# quad-wireless-switch.net
KiCad netlist of a schematic drawn in EAGLE
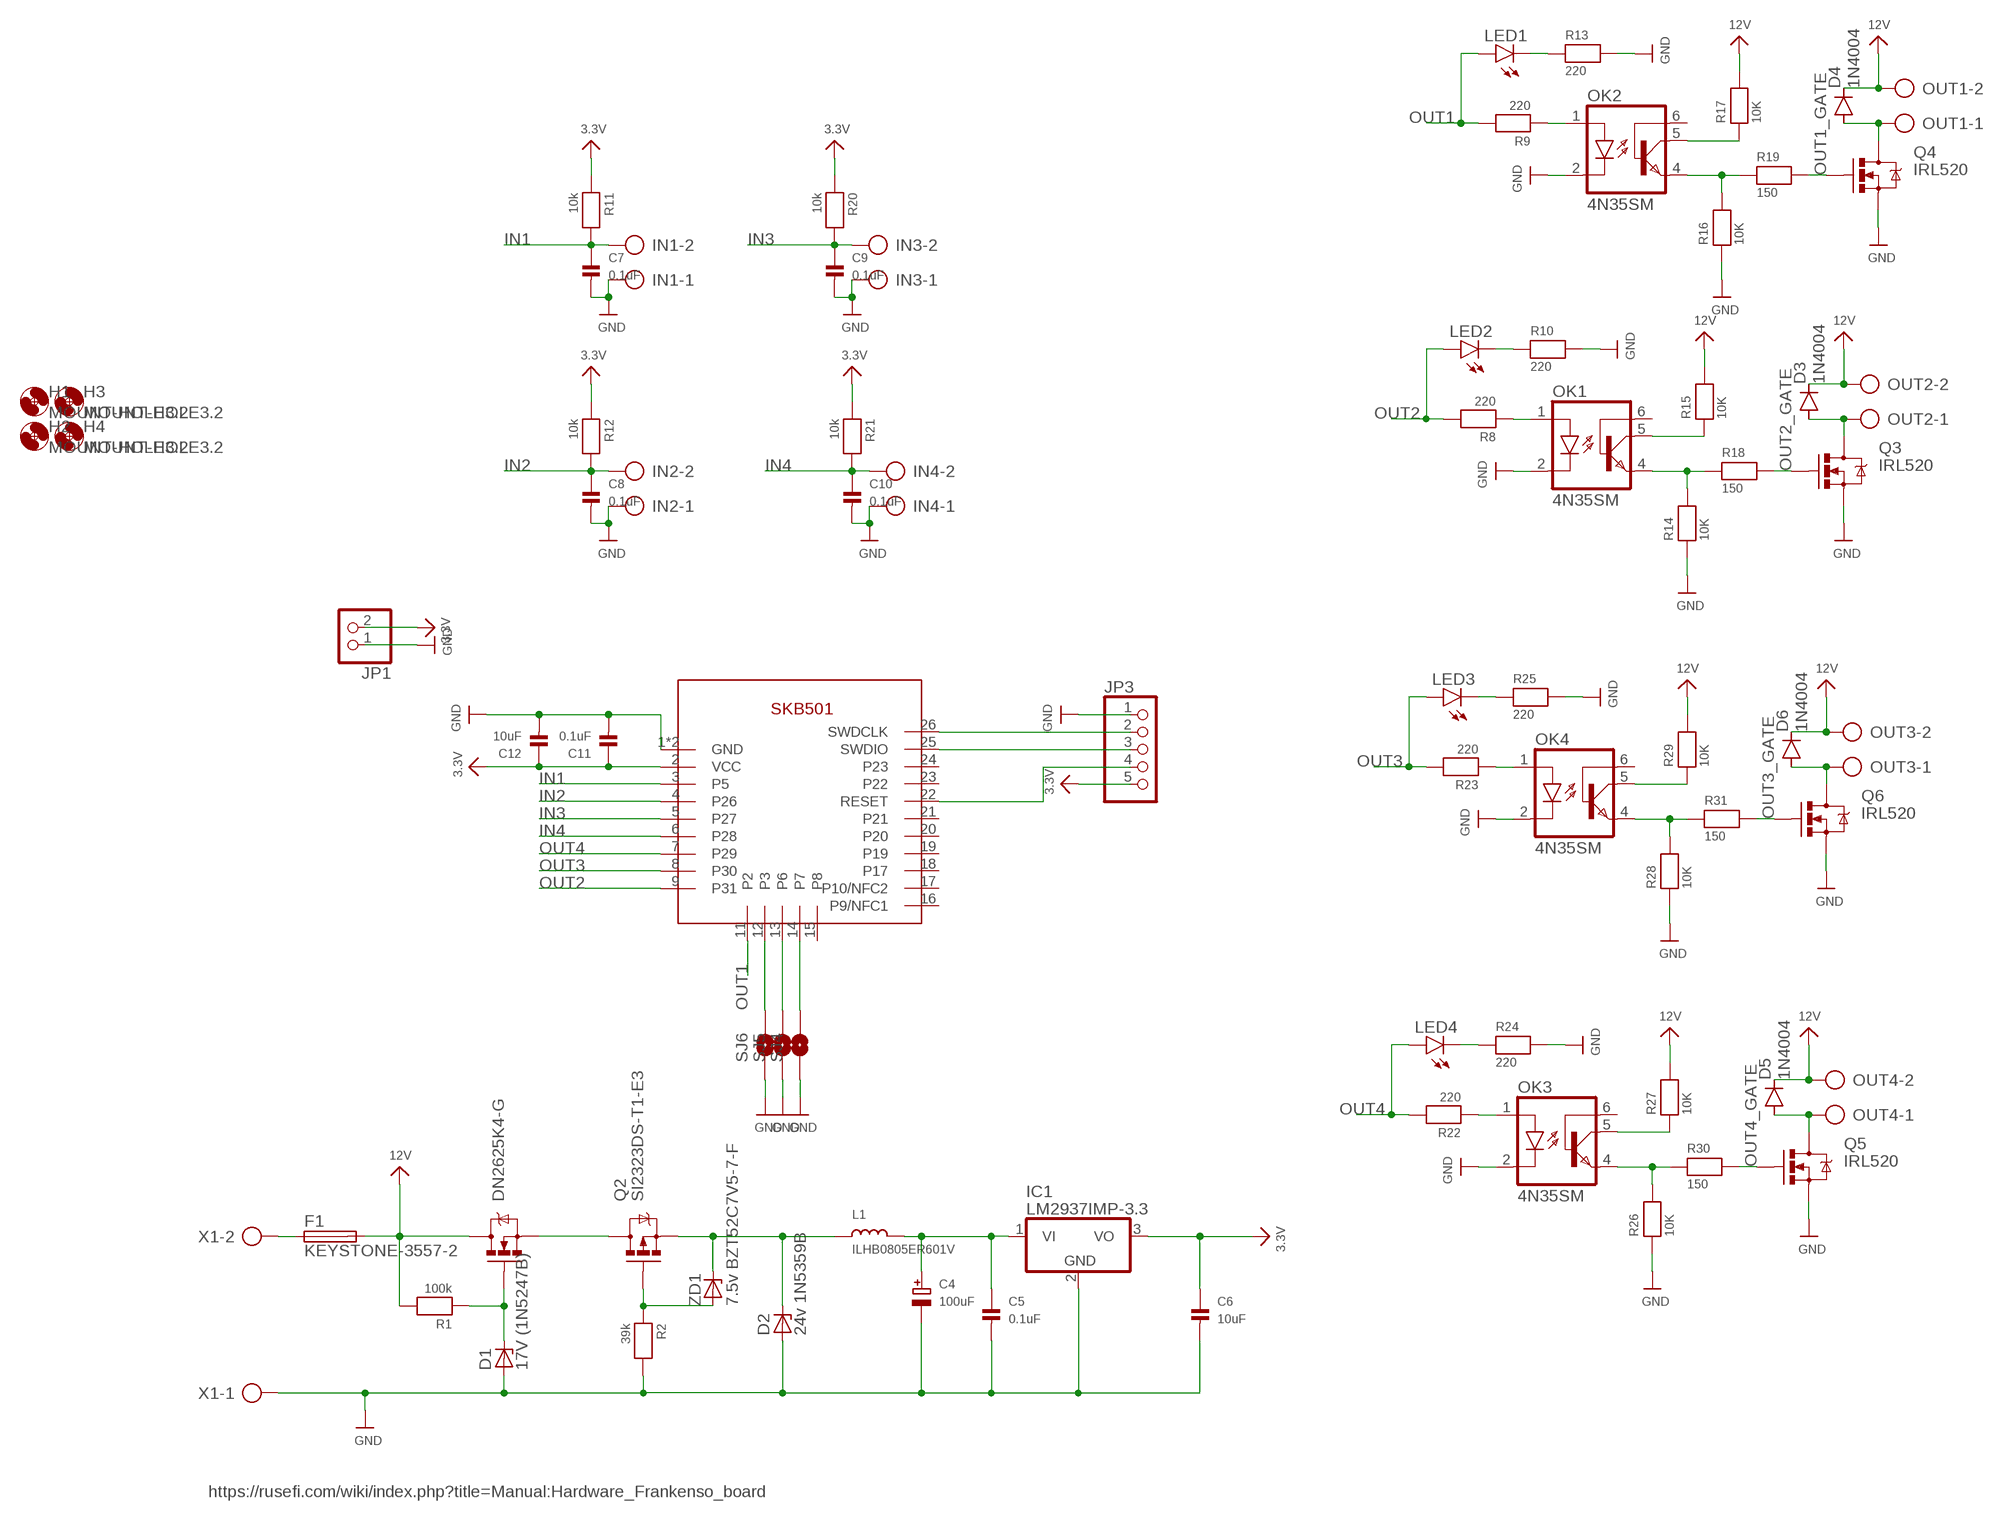
[diagram p0: schematic, sheet 1]

(export (version "E")
  (design (tool "Eeschema 10.0.6"))
  (components
    (comp (ref "C4")
      (value "100uF")
      (footprint "eagle-import:PANASONIC_D")
      (libsource (lib "eagle-import") (part "CAP_ELECTROLYTICPANASONIC_D"))
    )
    (comp (ref "C5")
      (value "0.1uF")
      (footprint "eagle-import:0805")
      (libsource (lib "eagle-import") (part "CAP_CERAMIC0805"))
    )
    (comp (ref "C6")
      (value "10uF")
      (footprint "eagle-import:0805")
      (libsource (lib "eagle-import") (part "CAP_CERAMIC0805"))
    )
    (comp (ref "C7")
      (value "0.1uF")
      (footprint "eagle-import:0805")
      (libsource (lib "eagle-import") (part "CAP_CERAMIC0805"))
    )
    (comp (ref "C8")
      (value "0.1uF")
      (footprint "eagle-import:0805")
      (libsource (lib "eagle-import") (part "CAP_CERAMIC0805"))
    )
    (comp (ref "C9")
      (value "0.1uF")
      (footprint "eagle-import:0805")
      (libsource (lib "eagle-import") (part "CAP_CERAMIC0805"))
    )
    (comp (ref "C10")
      (value "0.1uF")
      (footprint "eagle-import:0805")
      (libsource (lib "eagle-import") (part "CAP_CERAMIC0805"))
    )
    (comp (ref "C11")
      (value "0.1uF")
      (footprint "eagle-import:0805")
      (libsource (lib "eagle-import") (part "CAP_CERAMIC0805"))
    )
    (comp (ref "C12")
      (value "10uF")
      (footprint "eagle-import:0805")
      (libsource (lib "eagle-import") (part "CAP_CERAMIC0805"))
    )
    (comp (ref "D1")
      (value "17V (1N5247B)")
      (footprint "eagle-import:ZDIO-5")
      (libsource (lib "eagle-import") (part "ZENER-DIODEZD-5"))
    )
    (comp (ref "D2")
      (value "24v 1N5359B")
      (footprint "eagle-import:DO41Z10")
      (libsource (lib "eagle-import") (part "ZPY"))
    )
    (comp (ref "D3")
      (value "1N4004")
      (footprint "eagle-import:DO41-10")
      (libsource (lib "eagle-import") (part "1N4004"))
    )
    (comp (ref "D4")
      (value "1N4004")
      (footprint "eagle-import:DO41-10")
      (libsource (lib "eagle-import") (part "1N4004"))
    )
    (comp (ref "D5")
      (value "1N4004")
      (footprint "eagle-import:DO41-10")
      (libsource (lib "eagle-import") (part "1N4004"))
    )
    (comp (ref "D6")
      (value "1N4004")
      (footprint "eagle-import:DO41-10")
      (libsource (lib "eagle-import") (part "1N4004"))
    )
    (comp (ref "F1")
      (value "KEYSTONE-3557-2")
      (footprint "eagle-import:KEYSTONE-3557-2")
      (libsource (lib "eagle-import") (part "KEYSTONE-3557-2"))
    )
    (comp (ref "H1")
      (value "MOUNT-HOLE3.2")
      (footprint "eagle-import:3,2")
      (libsource (lib "eagle-import") (part "MOUNT-HOLE3.2"))
    )
    (comp (ref "H2")
      (value "MOUNT-HOLE3.2")
      (footprint "eagle-import:3,2")
      (libsource (lib "eagle-import") (part "MOUNT-HOLE3.2"))
    )
    (comp (ref "H3")
      (value "MOUNT-HOLE3.2")
      (footprint "eagle-import:3,2")
      (libsource (lib "eagle-import") (part "MOUNT-HOLE3.2"))
    )
    (comp (ref "H4")
      (value "MOUNT-HOLE3.2")
      (footprint "eagle-import:3,2")
      (libsource (lib "eagle-import") (part "MOUNT-HOLE3.2"))
    )
    (comp (ref "IC1")
      (value "LM2937IMP-3.3")
      (footprint "eagle-import:TO263-3")
      (libsource (lib "eagle-import") (part "LM2937"))
    )
    (comp (ref "IN1")
      (value "AK500/2-H")
      (footprint "eagle-import:AK500_2-H")
      (libsource (lib "eagle-import") (part "AK500/2-H"))
    )
    (comp (ref "IN2")
      (value "AK500/2-H")
      (footprint "eagle-import:AK500_2-H")
      (libsource (lib "eagle-import") (part "AK500/2-H"))
    )
    (comp (ref "IN3")
      (value "AK500/2-H")
      (footprint "eagle-import:AK500_2-H")
      (libsource (lib "eagle-import") (part "AK500/2-H"))
    )
    (comp (ref "IN4")
      (value "AK500/2-H")
      (footprint "eagle-import:AK500_2-H")
      (libsource (lib "eagle-import") (part "AK500/2-H"))
    )
    (comp (ref "JP1")
      (value "PINHD-1X2")
      (footprint "eagle-import:1X02")
      (libsource (lib "eagle-import") (part "PINHD-1X2"))
    )
    (comp (ref "JP3")
      (value "PINHD-1X5")
      (footprint "eagle-import:1X05")
      (libsource (lib "eagle-import") (part "PINHD-1X5"))
    )
    (comp (ref "L1")
      (value "ILHB0805ER601V")
      (footprint "eagle-import:0805")
      (libsource (lib "eagle-import") (part "INDUCTOR0805"))
    )
    (comp (ref "LED1")
      (value "LED5MM")
      (footprint "eagle-import:LED5MM")
      (libsource (lib "eagle-import") (part "LED5MM"))
    )
    (comp (ref "LED2")
      (value "LED5MM")
      (footprint "eagle-import:LED5MM")
      (libsource (lib "eagle-import") (part "LED5MM"))
    )
    (comp (ref "LED3")
      (value "LED5MM")
      (footprint "eagle-import:LED5MM")
      (libsource (lib "eagle-import") (part "LED5MM"))
    )
    (comp (ref "LED4")
      (value "LED5MM")
      (footprint "eagle-import:LED5MM")
      (libsource (lib "eagle-import") (part "LED5MM"))
    )
    (comp (ref "OK1")
      (value "4N35SM")
      (footprint "eagle-import:DIL6-SMD")
      (fields (field (name "MF") "FAIRCHILD SEMICONDUCTOR") (field (name "MPN") "4N35S-M"))
      (libsource (lib "eagle-import") (part "4N?MS35"))
    )
    (comp (ref "OK2")
      (value "4N35SM")
      (footprint "eagle-import:DIL6-SMD")
      (fields (field (name "MF") "FAIRCHILD SEMICONDUCTOR") (field (name "MPN") "4N35S-M"))
      (libsource (lib "eagle-import") (part "4N?MS35"))
    )
    (comp (ref "OK3")
      (value "4N35SM")
      (footprint "eagle-import:DIL6-SMD")
      (fields (field (name "MF") "FAIRCHILD SEMICONDUCTOR") (field (name "MPN") "4N35S-M"))
      (libsource (lib "eagle-import") (part "4N?MS35"))
    )
    (comp (ref "OK4")
      (value "4N35SM")
      (footprint "eagle-import:DIL6-SMD")
      (fields (field (name "MF") "FAIRCHILD SEMICONDUCTOR") (field (name "MPN") "4N35S-M"))
      (libsource (lib "eagle-import") (part "4N?MS35"))
    )
    (comp (ref "OUT1")
      (value "AK500/2-H")
      (footprint "eagle-import:AK500_2-H")
      (libsource (lib "eagle-import") (part "AK500/2-H"))
    )
    (comp (ref "OUT2")
      (value "AK500/2-H")
      (footprint "eagle-import:AK500_2-H")
      (libsource (lib "eagle-import") (part "AK500/2-H"))
    )
    (comp (ref "OUT3")
      (value "AK500/2-H")
      (footprint "eagle-import:AK500_2-H")
      (libsource (lib "eagle-import") (part "AK500/2-H"))
    )
    (comp (ref "OUT4")
      (value "AK500/2-H")
      (footprint "eagle-import:AK500_2-H")
      (libsource (lib "eagle-import") (part "AK500/2-H"))
    )
    (comp (ref "Q1")
      (value "DN2625K4-G")
      (footprint "eagle-import:DPAK")
      (libsource (lib "eagle-import") (part "MOSFET-NCHANNELFDD8780"))
    )
    (comp (ref "Q2")
      (value "SI2323DS-T1-E3")
      (footprint "eagle-import:SOT23-3")
      (libsource (lib "eagle-import") (part "MOSFET-PCHANNEL"))
    )
    (comp (ref "Q3")
      (value "IRL520")
      (footprint "eagle-import:TO220V")
      (libsource (lib "eagle-import") (part "keves-ng_1429743_MOSFET-NCHANNELFQP30N06L"))
    )
    (comp (ref "Q4")
      (value "IRL520")
      (footprint "eagle-import:TO220V")
      (libsource (lib "eagle-import") (part "keves-ng_1429743_MOSFET-NCHANNELFQP30N06L"))
    )
    (comp (ref "Q5")
      (value "IRL520")
      (footprint "eagle-import:TO220V")
      (libsource (lib "eagle-import") (part "keves-ng_1429743_MOSFET-NCHANNELFQP30N06L"))
    )
    (comp (ref "Q6")
      (value "IRL520")
      (footprint "eagle-import:TO220V")
      (libsource (lib "eagle-import") (part "keves-ng_1429743_MOSFET-NCHANNELFQP30N06L"))
    )
    (comp (ref "R1")
      (value "100k")
      (footprint "eagle-import:0805")
      (libsource (lib "eagle-import") (part "RESISTOR0805"))
    )
    (comp (ref "R2")
      (value "39k")
      (footprint "eagle-import:0805")
      (libsource (lib "eagle-import") (part "RESISTOR0805"))
    )
    (comp (ref "R8")
      (value "220")
      (footprint "eagle-import:0805")
      (libsource (lib "eagle-import") (part "RESISTOR0805"))
    )
    (comp (ref "R9")
      (value "220")
      (footprint "eagle-import:0805")
      (libsource (lib "eagle-import") (part "RESISTOR0805"))
    )
    (comp (ref "R10")
      (value "220")
      (footprint "eagle-import:0805")
      (libsource (lib "eagle-import") (part "RESISTOR0805"))
    )
    (comp (ref "R11")
      (value "10k")
      (footprint "eagle-import:0805")
      (libsource (lib "eagle-import") (part "RESISTOR0805"))
    )
    (comp (ref "R12")
      (value "10k")
      (footprint "eagle-import:0805")
      (libsource (lib "eagle-import") (part "RESISTOR0805"))
    )
    (comp (ref "R13")
      (value "220")
      (footprint "eagle-import:0805")
      (libsource (lib "eagle-import") (part "RESISTOR0805"))
    )
    (comp (ref "R14")
      (value "10K")
      (footprint "eagle-import:0805")
      (libsource (lib "eagle-import") (part "RESISTOR0805"))
    )
    (comp (ref "R15")
      (value "10K")
      (footprint "eagle-import:0805")
      (libsource (lib "eagle-import") (part "RESISTOR0805"))
    )
    (comp (ref "R16")
      (value "10K")
      (footprint "eagle-import:0805")
      (libsource (lib "eagle-import") (part "RESISTOR0805"))
    )
    (comp (ref "R17")
      (value "10K")
      (footprint "eagle-import:0805")
      (libsource (lib "eagle-import") (part "RESISTOR0805"))
    )
    (comp (ref "R18")
      (value "150")
      (footprint "eagle-import:0805")
      (libsource (lib "eagle-import") (part "RESISTOR0805"))
    )
    (comp (ref "R19")
      (value "150")
      (footprint "eagle-import:0805")
      (libsource (lib "eagle-import") (part "RESISTOR0805"))
    )
    (comp (ref "R20")
      (value "10k")
      (footprint "eagle-import:0805")
      (libsource (lib "eagle-import") (part "RESISTOR0805"))
    )
    (comp (ref "R21")
      (value "10k")
      (footprint "eagle-import:0805")
      (libsource (lib "eagle-import") (part "RESISTOR0805"))
    )
    (comp (ref "R22")
      (value "220")
      (footprint "eagle-import:0805")
      (libsource (lib "eagle-import") (part "RESISTOR0805"))
    )
    (comp (ref "R23")
      (value "220")
      (footprint "eagle-import:0805")
      (libsource (lib "eagle-import") (part "RESISTOR0805"))
    )
    (comp (ref "R24")
      (value "220")
      (footprint "eagle-import:0805")
      (libsource (lib "eagle-import") (part "RESISTOR0805"))
    )
    (comp (ref "R25")
      (value "220")
      (footprint "eagle-import:0805")
      (libsource (lib "eagle-import") (part "RESISTOR0805"))
    )
    (comp (ref "R26")
      (value "10K")
      (footprint "eagle-import:0805")
      (libsource (lib "eagle-import") (part "RESISTOR0805"))
    )
    (comp (ref "R27")
      (value "10K")
      (footprint "eagle-import:0805")
      (libsource (lib "eagle-import") (part "RESISTOR0805"))
    )
    (comp (ref "R28")
      (value "10K")
      (footprint "eagle-import:0805")
      (libsource (lib "eagle-import") (part "RESISTOR0805"))
    )
    (comp (ref "R29")
      (value "10K")
      (footprint "eagle-import:0805")
      (libsource (lib "eagle-import") (part "RESISTOR0805"))
    )
    (comp (ref "R30")
      (value "150")
      (footprint "eagle-import:0805")
      (libsource (lib "eagle-import") (part "RESISTOR0805"))
    )
    (comp (ref "R31")
      (value "150")
      (footprint "eagle-import:0805")
      (libsource (lib "eagle-import") (part "RESISTOR0805"))
    )
    (comp (ref "SJ4")
      (value "SOLDERJUMPERNO")
      (footprint "eagle-import:SJ_2S-NO")
      (libsource (lib "eagle-import") (part "SOLDERJUMPERNO"))
    )
    (comp (ref "SJ5")
      (value "SOLDERJUMPERNO")
      (footprint "eagle-import:SJ_2S-NO")
      (libsource (lib "eagle-import") (part "SOLDERJUMPERNO"))
    )
    (comp (ref "SJ6")
      (value "SOLDERJUMPERNO")
      (footprint "eagle-import:SJ_2S-NO")
      (libsource (lib "eagle-import") (part "SOLDERJUMPERNO"))
    )
    (comp (ref "U2")
      (value "SDB501")
      (footprint "eagle-import:SKB501")
      (libsource (lib "eagle-import") (part "SDB501"))
    )
    (comp (ref "X1")
      (value "AK500/2-H")
      (footprint "eagle-import:AK500_2-H")
      (libsource (lib "eagle-import") (part "AK500/2-H"))
    )
    (comp (ref "ZD1")
      (value "7.5v BZT52C7V5-7-F")
      (footprint "eagle-import:SOD123")
      (libsource (lib "eagle-import") (part "ZD-SOD123"))
    )
  )
  (nets
    (net (code "1") (name "/IN1") (class "Default")
      (node (ref "C7") (pin "1") (pinfunction "P$1_1") (pintype "passive"))
      (node (ref "IN1") (pin "2") (pinfunction "KL_2") (pintype "passive"))
      (node (ref "R11") (pin "2") (pinfunction "2_2") (pintype "passive"))
      (node (ref "U2") (pin "3") (pinfunction "P5_3") (pintype "bidirectional"))
    )
    (net (code "2") (name "/IN2") (class "Default")
      (node (ref "C8") (pin "1") (pinfunction "P$1_1") (pintype "passive"))
      (node (ref "IN2") (pin "2") (pinfunction "KL_2") (pintype "passive"))
      (node (ref "R12") (pin "2") (pinfunction "2_2") (pintype "passive"))
      (node (ref "U2") (pin "4") (pinfunction "P26_4") (pintype "bidirectional"))
    )
    (net (code "3") (name "/IN3") (class "Default")
      (node (ref "C9") (pin "1") (pinfunction "P$1_1") (pintype "passive"))
      (node (ref "IN3") (pin "2") (pinfunction "KL_2") (pintype "passive"))
      (node (ref "R20") (pin "2") (pinfunction "2_2") (pintype "passive"))
      (node (ref "U2") (pin "5") (pinfunction "P27_5") (pintype "bidirectional"))
    )
    (net (code "4") (name "/IN4") (class "Default")
      (node (ref "C10") (pin "1") (pinfunction "P$1_1") (pintype "passive"))
      (node (ref "IN4") (pin "2") (pinfunction "KL_2") (pintype "passive"))
      (node (ref "R21") (pin "2") (pinfunction "2_2") (pintype "passive"))
      (node (ref "U2") (pin "6") (pinfunction "P28_6") (pintype "bidirectional"))
    )
    (net (code "5") (name "/OUT1") (class "Default")
      (node (ref "LED1") (pin "A") (pinfunction "A_A") (pintype "passive"))
      (node (ref "R9") (pin "2") (pinfunction "2_2") (pintype "passive"))
      (node (ref "U2") (pin "11") (pinfunction "P2_11") (pintype "bidirectional"))
    )
    (net (code "6") (name "/OUT1_GATE") (class "Default")
      (node (ref "Q4") (pin "1") (pinfunction "G_1") (pintype "passive"))
      (node (ref "R19") (pin "2") (pinfunction "2_2") (pintype "passive"))
    )
    (net (code "7") (name "/OUT2") (class "Default")
      (node (ref "LED2") (pin "A") (pinfunction "A_A") (pintype "passive"))
      (node (ref "R8") (pin "2") (pinfunction "2_2") (pintype "passive"))
      (node (ref "U2") (pin "9") (pinfunction "P31_9") (pintype "bidirectional"))
    )
    (net (code "8") (name "/OUT2_GATE") (class "Default")
      (node (ref "Q3") (pin "1") (pinfunction "G_1") (pintype "passive"))
      (node (ref "R18") (pin "2") (pinfunction "2_2") (pintype "passive"))
    )
    (net (code "9") (name "/OUT3") (class "Default")
      (node (ref "LED3") (pin "A") (pinfunction "A_A") (pintype "passive"))
      (node (ref "R23") (pin "2") (pinfunction "2_2") (pintype "passive"))
      (node (ref "U2") (pin "8") (pinfunction "P30_8") (pintype "bidirectional"))
    )
    (net (code "10") (name "/OUT3_GATE") (class "Default")
      (node (ref "Q6") (pin "1") (pinfunction "G_1") (pintype "passive"))
      (node (ref "R31") (pin "2") (pinfunction "2_2") (pintype "passive"))
    )
    (net (code "11") (name "/OUT4") (class "Default")
      (node (ref "LED4") (pin "A") (pinfunction "A_A") (pintype "passive"))
      (node (ref "R22") (pin "2") (pinfunction "2_2") (pintype "passive"))
      (node (ref "U2") (pin "7") (pinfunction "P29_7") (pintype "bidirectional"))
    )
    (net (code "12") (name "/OUT4_GATE") (class "Default")
      (node (ref "Q5") (pin "1") (pinfunction "G_1") (pintype "passive"))
      (node (ref "R30") (pin "2") (pinfunction "2_2") (pintype "passive"))
    )
    (net (code "13") (name "3.3V") (class "Default")
      (node (ref "C11") (pin "1") (pinfunction "P$1_1") (pintype "passive"))
      (node (ref "C12") (pin "1") (pinfunction "P$1_1") (pintype "passive"))
      (node (ref "C6") (pin "1") (pinfunction "P$1_1") (pintype "passive"))
      (node (ref "IC1") (pin "3") (pinfunction "VO_3") (pintype "passive"))
      (node (ref "JP1") (pin "2") (pinfunction "2_2") (pintype "passive"))
      (node (ref "JP3") (pin "5") (pinfunction "5_5") (pintype "passive"))
      (node (ref "R11") (pin "1") (pinfunction "1_1") (pintype "passive"))
      (node (ref "R12") (pin "1") (pinfunction "1_1") (pintype "passive"))
      (node (ref "R20") (pin "1") (pinfunction "1_1") (pintype "passive"))
      (node (ref "R21") (pin "1") (pinfunction "1_1") (pintype "passive"))
      (node (ref "U2") (pin "2") (pinfunction "VCC_2") (pintype "bidirectional"))
    )
    (net (code "14") (name "12V") (class "Default")
      (node (ref "D3") (pin "C") (pinfunction "C_C") (pintype "passive"))
      (node (ref "D4") (pin "C") (pinfunction "C_C") (pintype "passive"))
      (node (ref "D5") (pin "C") (pinfunction "C_C") (pintype "passive"))
      (node (ref "D6") (pin "C") (pinfunction "C_C") (pintype "passive"))
      (node (ref "F1") (pin "R1") (pinfunction "2_R1") (pintype "passive"))
      (node (ref "F1") (pin "R2") (pinfunction "2_R2") (pintype "passive"))
      (node (ref "OUT1") (pin "2") (pinfunction "KL_2") (pintype "passive"))
      (node (ref "OUT2") (pin "2") (pinfunction "KL_2") (pintype "passive"))
      (node (ref "OUT3") (pin "2") (pinfunction "KL_2") (pintype "passive"))
      (node (ref "OUT4") (pin "2") (pinfunction "KL_2") (pintype "passive"))
      (node (ref "Q1") (pin "4") (pinfunction "D_4") (pintype "passive"))
      (node (ref "R1") (pin "2") (pinfunction "2_2") (pintype "passive"))
      (node (ref "R15") (pin "2") (pinfunction "2_2") (pintype "passive"))
      (node (ref "R17") (pin "2") (pinfunction "2_2") (pintype "passive"))
      (node (ref "R27") (pin "2") (pinfunction "2_2") (pintype "passive"))
      (node (ref "R29") (pin "2") (pinfunction "2_2") (pintype "passive"))
    )
    (net (code "15") (name "GND") (class "Default")
      (node (ref "C10") (pin "2") (pinfunction "P$2_2") (pintype "passive"))
      (node (ref "C11") (pin "2") (pinfunction "P$2_2") (pintype "passive"))
      (node (ref "C12") (pin "2") (pinfunction "P$2_2") (pintype "passive"))
      (node (ref "C4") (pin "-") (pinfunction "-_-") (pintype "passive"))
      (node (ref "C5") (pin "2") (pinfunction "P$2_2") (pintype "passive"))
      (node (ref "C6") (pin "2") (pinfunction "P$2_2") (pintype "passive"))
      (node (ref "C7") (pin "2") (pinfunction "P$2_2") (pintype "passive"))
      (node (ref "C8") (pin "2") (pinfunction "P$2_2") (pintype "passive"))
      (node (ref "C9") (pin "2") (pinfunction "P$2_2") (pintype "passive"))
      (node (ref "D1") (pin "A") (pinfunction "A_A") (pintype "passive"))
      (node (ref "D2") (pin "A") (pinfunction "A_A") (pintype "passive"))
      (node (ref "IC1") (pin "2") (pinfunction "GND_2") (pintype "passive"))
      (node (ref "IN1") (pin "1") (pinfunction "KL_1") (pintype "passive"))
      (node (ref "IN2") (pin "1") (pinfunction "KL_1") (pintype "passive"))
      (node (ref "IN3") (pin "1") (pinfunction "KL_1") (pintype "passive"))
      (node (ref "IN4") (pin "1") (pinfunction "KL_1") (pintype "passive"))
      (node (ref "JP1") (pin "1") (pinfunction "1_1") (pintype "passive"))
      (node (ref "JP3") (pin "1") (pinfunction "1_1") (pintype "passive"))
      (node (ref "OK1") (pin "2") (pinfunction "C_2") (pintype "passive"))
      (node (ref "OK2") (pin "2") (pinfunction "C_2") (pintype "passive"))
      (node (ref "OK3") (pin "2") (pinfunction "C_2") (pintype "passive"))
      (node (ref "OK4") (pin "2") (pinfunction "C_2") (pintype "passive"))
      (node (ref "Q3") (pin "3") (pinfunction "S_3") (pintype "passive"))
      (node (ref "Q4") (pin "3") (pinfunction "S_3") (pintype "passive"))
      (node (ref "Q5") (pin "3") (pinfunction "S_3") (pintype "passive"))
      (node (ref "Q6") (pin "3") (pinfunction "S_3") (pintype "passive"))
      (node (ref "R10") (pin "2") (pinfunction "2_2") (pintype "passive"))
      (node (ref "R13") (pin "2") (pinfunction "2_2") (pintype "passive"))
      (node (ref "R14") (pin "1") (pinfunction "1_1") (pintype "passive"))
      (node (ref "R16") (pin "1") (pinfunction "1_1") (pintype "passive"))
      (node (ref "R2") (pin "2") (pinfunction "2_2") (pintype "passive"))
      (node (ref "R24") (pin "2") (pinfunction "2_2") (pintype "passive"))
      (node (ref "R25") (pin "2") (pinfunction "2_2") (pintype "passive"))
      (node (ref "R26") (pin "1") (pinfunction "1_1") (pintype "passive"))
      (node (ref "R28") (pin "1") (pinfunction "1_1") (pintype "passive"))
      (node (ref "SJ4") (pin "1") (pinfunction "1_1") (pintype "passive"))
      (node (ref "SJ5") (pin "1") (pinfunction "1_1") (pintype "passive"))
      (node (ref "SJ6") (pin "1") (pinfunction "1_1") (pintype "passive"))
      (node (ref "U2") (pin "1") (pinfunction "GND_1") (pintype "bidirectional"))
      (node (ref "U2") (pin "10") (pinfunction "GND_10") (pintype "bidirectional"))
      (node (ref "X1") (pin "1") (pinfunction "KL_1") (pintype "passive"))
    )
    (net (code "16") (name "Net-(C5-P$1)") (class "Default")
      (node (ref "C4") (pin "+") (pinfunction "+_+") (pintype "passive"))
      (node (ref "C5") (pin "1") (pinfunction "P$1_1") (pintype "passive"))
      (node (ref "IC1") (pin "1") (pinfunction "VI_1") (pintype "input"))
      (node (ref "L1") (pin "2") (pinfunction "2_2") (pintype "passive"))
    )
    (net (code "17") (name "Net-(LED1-C)") (class "Default")
      (node (ref "LED1") (pin "K") (pinfunction "C_K") (pintype "passive"))
      (node (ref "R13") (pin "1") (pinfunction "1_1") (pintype "passive"))
    )
    (net (code "18") (name "Net-(LED2-C)") (class "Default")
      (node (ref "LED2") (pin "K") (pinfunction "C_K") (pintype "passive"))
      (node (ref "R10") (pin "1") (pinfunction "1_1") (pintype "passive"))
    )
    (net (code "19") (name "Net-(LED3-C)") (class "Default")
      (node (ref "LED3") (pin "K") (pinfunction "C_K") (pintype "passive"))
      (node (ref "R25") (pin "1") (pinfunction "1_1") (pintype "passive"))
    )
    (net (code "20") (name "Net-(LED4-C)") (class "Default")
      (node (ref "LED4") (pin "K") (pinfunction "C_K") (pintype "passive"))
      (node (ref "R24") (pin "1") (pinfunction "1_1") (pintype "passive"))
    )
    (net (code "21") (name "Net-(OK1-A)") (class "Default")
      (node (ref "OK1") (pin "1") (pinfunction "A_1") (pintype "passive"))
      (node (ref "R8") (pin "1") (pinfunction "1_1") (pintype "passive"))
    )
    (net (code "22") (name "Net-(OK1-COL)") (class "Default")
      (node (ref "OK1") (pin "5") (pinfunction "COL_5") (pintype "passive"))
      (node (ref "R15") (pin "1") (pinfunction "1_1") (pintype "passive"))
    )
    (net (code "23") (name "Net-(OK1-EMI)") (class "Default")
      (node (ref "OK1") (pin "4") (pinfunction "EMI_4") (pintype "passive"))
      (node (ref "R14") (pin "2") (pinfunction "2_2") (pintype "passive"))
      (node (ref "R18") (pin "1") (pinfunction "1_1") (pintype "passive"))
    )
    (net (code "24") (name "Net-(OK2-A)") (class "Default")
      (node (ref "OK2") (pin "1") (pinfunction "A_1") (pintype "passive"))
      (node (ref "R9") (pin "1") (pinfunction "1_1") (pintype "passive"))
    )
    (net (code "25") (name "Net-(OK2-COL)") (class "Default")
      (node (ref "OK2") (pin "5") (pinfunction "COL_5") (pintype "passive"))
      (node (ref "R17") (pin "1") (pinfunction "1_1") (pintype "passive"))
    )
    (net (code "26") (name "Net-(OK2-EMI)") (class "Default")
      (node (ref "OK2") (pin "4") (pinfunction "EMI_4") (pintype "passive"))
      (node (ref "R16") (pin "2") (pinfunction "2_2") (pintype "passive"))
      (node (ref "R19") (pin "1") (pinfunction "1_1") (pintype "passive"))
    )
    (net (code "27") (name "Net-(OK3-A)") (class "Default")
      (node (ref "OK3") (pin "1") (pinfunction "A_1") (pintype "passive"))
      (node (ref "R22") (pin "1") (pinfunction "1_1") (pintype "passive"))
    )
    (net (code "28") (name "Net-(OK3-COL)") (class "Default")
      (node (ref "OK3") (pin "5") (pinfunction "COL_5") (pintype "passive"))
      (node (ref "R27") (pin "1") (pinfunction "1_1") (pintype "passive"))
    )
    (net (code "29") (name "Net-(OK3-EMI)") (class "Default")
      (node (ref "OK3") (pin "4") (pinfunction "EMI_4") (pintype "passive"))
      (node (ref "R26") (pin "2") (pinfunction "2_2") (pintype "passive"))
      (node (ref "R30") (pin "1") (pinfunction "1_1") (pintype "passive"))
    )
    (net (code "30") (name "Net-(OK4-A)") (class "Default")
      (node (ref "OK4") (pin "1") (pinfunction "A_1") (pintype "passive"))
      (node (ref "R23") (pin "1") (pinfunction "1_1") (pintype "passive"))
    )
    (net (code "31") (name "Net-(OK4-COL)") (class "Default")
      (node (ref "OK4") (pin "5") (pinfunction "COL_5") (pintype "passive"))
      (node (ref "R29") (pin "1") (pinfunction "1_1") (pintype "passive"))
    )
    (net (code "32") (name "Net-(OK4-EMI)") (class "Default")
      (node (ref "OK4") (pin "4") (pinfunction "EMI_4") (pintype "passive"))
      (node (ref "R28") (pin "2") (pinfunction "2_2") (pintype "passive"))
      (node (ref "R31") (pin "1") (pinfunction "1_1") (pintype "passive"))
    )
    (net (code "33") (name "Net-(OUT1A-KL)") (class "Default")
      (node (ref "D4") (pin "A") (pinfunction "A_A") (pintype "passive"))
      (node (ref "OUT1") (pin "1") (pinfunction "KL_1") (pintype "passive"))
      (node (ref "Q4") (pin "2") (pinfunction "D_2") (pintype "passive"))
    )
    (net (code "34") (name "Net-(OUT2A-KL)") (class "Default")
      (node (ref "D3") (pin "A") (pinfunction "A_A") (pintype "passive"))
      (node (ref "OUT2") (pin "1") (pinfunction "KL_1") (pintype "passive"))
      (node (ref "Q3") (pin "2") (pinfunction "D_2") (pintype "passive"))
    )
    (net (code "35") (name "Net-(OUT3A-KL)") (class "Default")
      (node (ref "D6") (pin "A") (pinfunction "A_A") (pintype "passive"))
      (node (ref "OUT3") (pin "1") (pinfunction "KL_1") (pintype "passive"))
      (node (ref "Q6") (pin "2") (pinfunction "D_2") (pintype "passive"))
    )
    (net (code "36") (name "Net-(OUT4A-KL)") (class "Default")
      (node (ref "D5") (pin "A") (pinfunction "A_A") (pintype "passive"))
      (node (ref "OUT4") (pin "1") (pinfunction "KL_1") (pintype "passive"))
      (node (ref "Q5") (pin "2") (pinfunction "D_2") (pintype "passive"))
    )
    (net (code "37") (name "Net-(Q1-G)") (class "Default")
      (node (ref "D1") (pin "C") (pinfunction "C_C") (pintype "passive"))
      (node (ref "Q1") (pin "1") (pinfunction "G_1") (pintype "passive"))
      (node (ref "R1") (pin "1") (pinfunction "1_1") (pintype "passive"))
    )
    (net (code "38") (name "Net-(Q1-S)") (class "Default")
      (node (ref "Q1") (pin "3") (pinfunction "S_3") (pintype "passive"))
      (node (ref "Q2") (pin "3") (pinfunction "D_3") (pintype "passive"))
    )
    (net (code "39") (name "Net-(Q2-G)") (class "Default")
      (node (ref "Q2") (pin "1") (pinfunction "G_1") (pintype "passive"))
      (node (ref "R2") (pin "1") (pinfunction "1_1") (pintype "passive"))
      (node (ref "ZD1") (pin "A") (pinfunction "A_A") (pintype "passive"))
    )
    (net (code "40") (name "Net-(Q2-S)") (class "Default")
      (node (ref "D2") (pin "C") (pinfunction "C_C") (pintype "passive"))
      (node (ref "L1") (pin "1") (pinfunction "1_1") (pintype "passive"))
      (node (ref "Q2") (pin "2") (pinfunction "S_2") (pintype "passive"))
      (node (ref "ZD1") (pin "C") (pinfunction "C_C") (pintype "passive"))
    )
    (net (code "41") (name "Net-(U2-P3)") (class "Default")
      (node (ref "SJ6") (pin "2") (pinfunction "2_2") (pintype "passive"))
      (node (ref "U2") (pin "12") (pinfunction "P3_12") (pintype "bidirectional"))
    )
    (net (code "42") (name "Net-(U2-P6)") (class "Default")
      (node (ref "SJ5") (pin "2") (pinfunction "2_2") (pintype "passive"))
      (node (ref "U2") (pin "13") (pinfunction "P6_13") (pintype "bidirectional"))
    )
    (net (code "43") (name "Net-(U2-P7)") (class "Default")
      (node (ref "SJ4") (pin "2") (pinfunction "2_2") (pintype "passive"))
      (node (ref "U2") (pin "14") (pinfunction "P7_14") (pintype "bidirectional"))
    )
    (net (code "44") (name "Net-(U2-RESET)") (class "Default")
      (node (ref "JP3") (pin "4") (pinfunction "4_4") (pintype "passive"))
      (node (ref "U2") (pin "22") (pinfunction "RESET_22") (pintype "bidirectional"))
    )
    (net (code "45") (name "Net-(U2-SWDCLK)") (class "Default")
      (node (ref "JP3") (pin "2") (pinfunction "2_2") (pintype "passive"))
      (node (ref "U2") (pin "26") (pinfunction "SWDCLK_26") (pintype "bidirectional"))
    )
    (net (code "46") (name "Net-(U2-SWDIO)") (class "Default")
      (node (ref "JP3") (pin "3") (pinfunction "3_3") (pintype "passive"))
      (node (ref "U2") (pin "25") (pinfunction "SWDIO_25") (pintype "bidirectional"))
    )
    (net (code "47") (name "Net-(X1B-KL)") (class "Default")
      (node (ref "F1") (pin "L1") (pinfunction "1_L1") (pintype "passive"))
      (node (ref "F1") (pin "L2") (pinfunction "1_L2") (pintype "passive"))
      (node (ref "X1") (pin "2") (pinfunction "KL_2") (pintype "passive"))
    )
    (net (code "48") (name "unconnected-(OK1-BAS-Pad6)") (class "Default")
      (node (ref "OK1") (pin "6") (pinfunction "BAS_6") (pintype "passive"))
    )
    (net (code "49") (name "unconnected-(OK2-BAS-Pad6)") (class "Default")
      (node (ref "OK2") (pin "6") (pinfunction "BAS_6") (pintype "passive"))
    )
    (net (code "50") (name "unconnected-(OK3-BAS-Pad6)") (class "Default")
      (node (ref "OK3") (pin "6") (pinfunction "BAS_6") (pintype "passive"))
    )
    (net (code "51") (name "unconnected-(OK4-BAS-Pad6)") (class "Default")
      (node (ref "OK4") (pin "6") (pinfunction "BAS_6") (pintype "passive"))
    )
    (net (code "52") (name "unconnected-(U2-P8-Pad15)") (class "Default")
      (node (ref "U2") (pin "15") (pinfunction "P8_15") (pintype "bidirectional"))
    )
    (net (code "53") (name "unconnected-(U2-P9{slash}NFC1-Pad16)") (class "Default")
      (node (ref "U2") (pin "16") (pinfunction "P9/NFC1_16") (pintype "bidirectional"))
    )
    (net (code "54") (name "unconnected-(U2-P10{slash}NFC2-Pad17)") (class "Default")
      (node (ref "U2") (pin "17") (pinfunction "P10/NFC2_17") (pintype "bidirectional"))
    )
    (net (code "55") (name "unconnected-(U2-P17-Pad18)") (class "Default")
      (node (ref "U2") (pin "18") (pinfunction "P17_18") (pintype "bidirectional"))
    )
    (net (code "56") (name "unconnected-(U2-P19-Pad19)") (class "Default")
      (node (ref "U2") (pin "19") (pinfunction "P19_19") (pintype "bidirectional"))
    )
    (net (code "57") (name "unconnected-(U2-P20-Pad20)") (class "Default")
      (node (ref "U2") (pin "20") (pinfunction "P20_20") (pintype "bidirectional"))
    )
    (net (code "58") (name "unconnected-(U2-P21-Pad21)") (class "Default")
      (node (ref "U2") (pin "21") (pinfunction "P21_21") (pintype "bidirectional"))
    )
    (net (code "59") (name "unconnected-(U2-P22-Pad23)") (class "Default")
      (node (ref "U2") (pin "23") (pinfunction "P22_23") (pintype "bidirectional"))
    )
    (net (code "60") (name "unconnected-(U2-P23-Pad24)") (class "Default")
      (node (ref "U2") (pin "24") (pinfunction "P23_24") (pintype "bidirectional"))
    )
  )
)
